# arduino_irobot_bridge.net
KiCad netlist of a schematic drawn in EAGLE
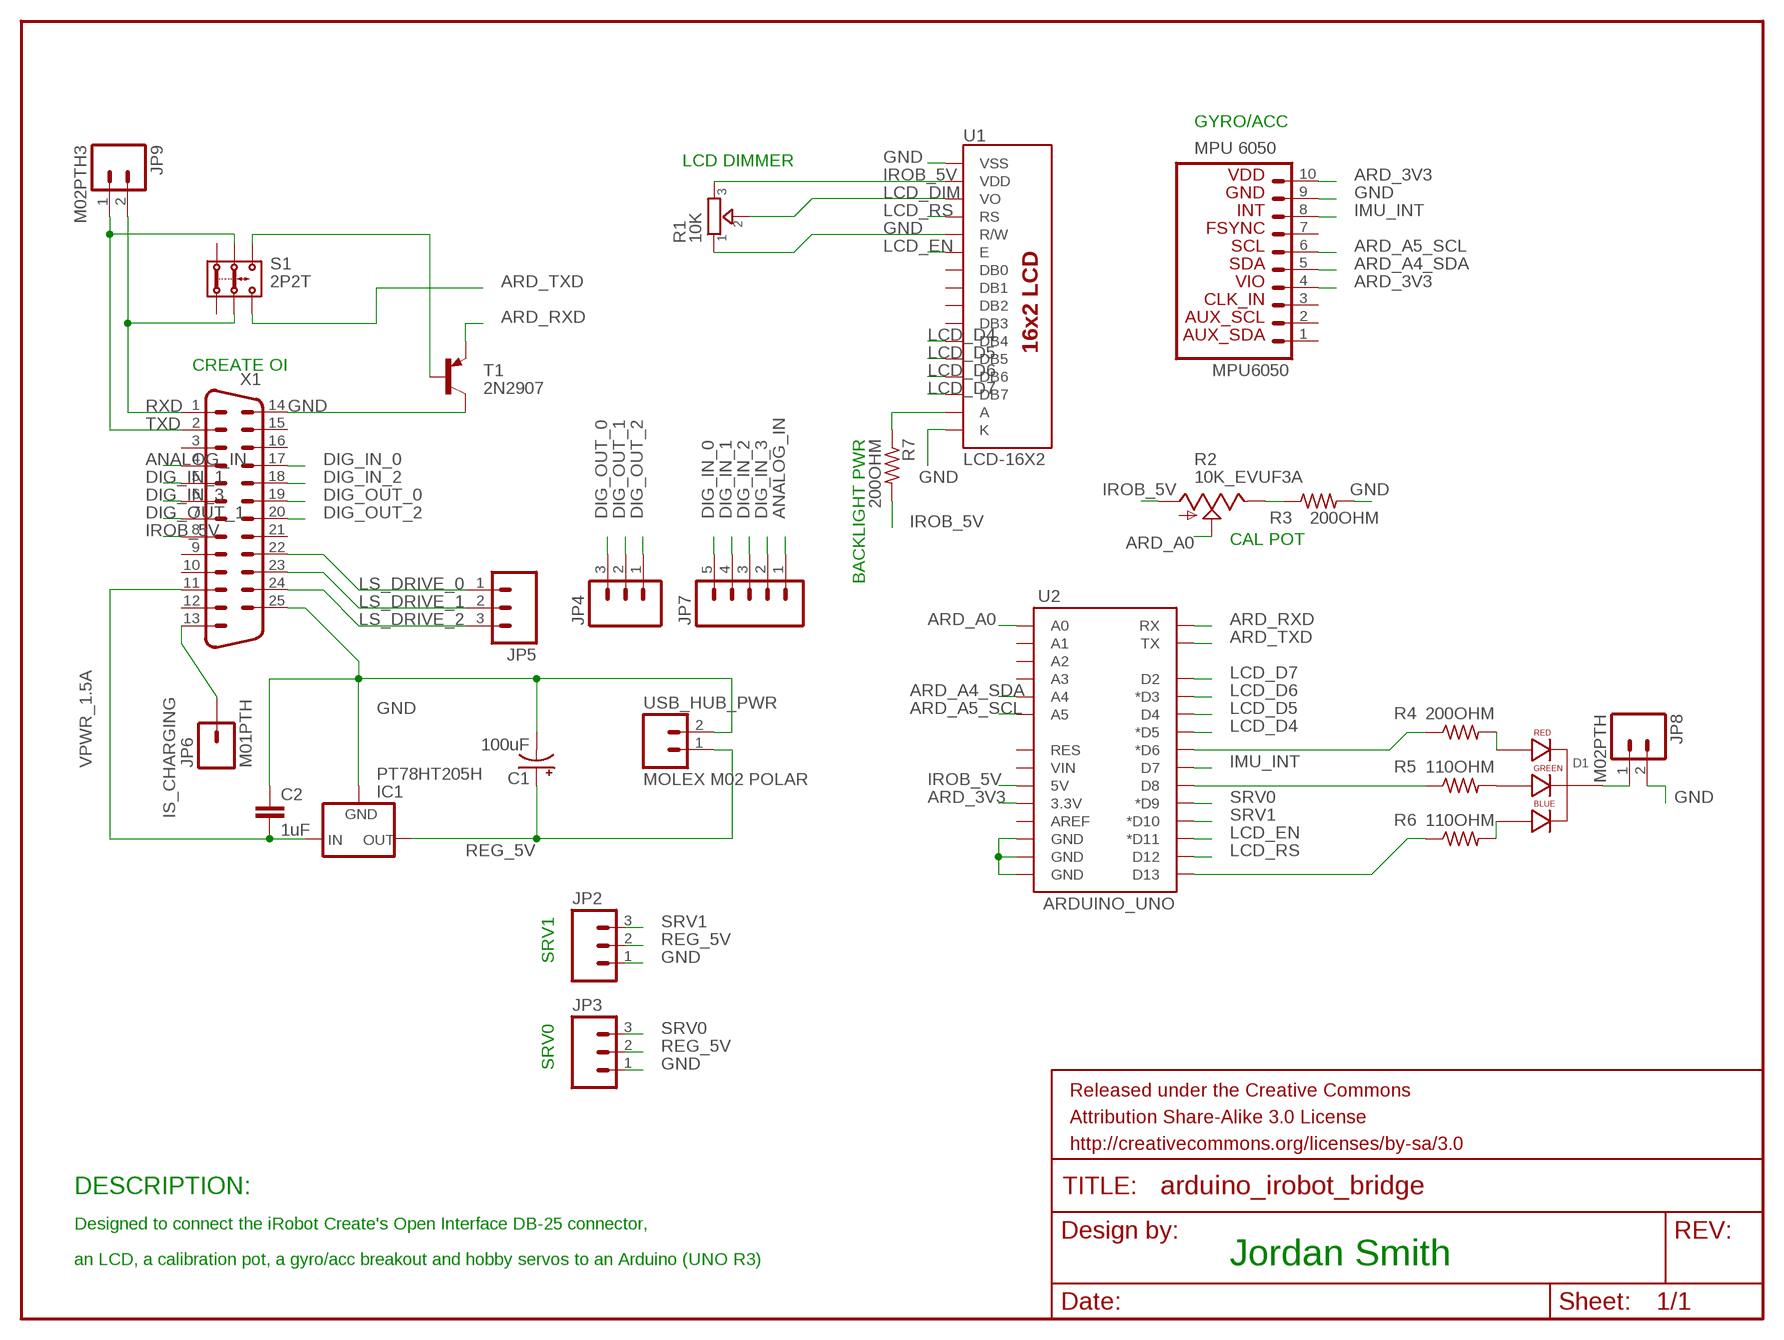
[diagram p0: schematic, sheet 1]

(export (version "E")
  (design (tool "Eeschema 10.0.6"))
  (components
    (comp (ref "C1")
      (value "100uF")
      (footprint "eagle-import:CPOL-RADIAL-100UF-25V")
      (libsource (lib "eagle-import") (part "CAP_POLPTH1"))
    )
    (comp (ref "C2")
      (value "1uF")
      (footprint "eagle-import:C2.5-2")
      (libsource (lib "eagle-import") (part "C2.5/2"))
    )
    (comp (ref "D1")
      (value "LED-RGB-CC-THRUCLEAR")
      (footprint "eagle-import:LED-RGB-THRU")
      (fields (field (name "PROD_ID") "DIO-08418"))
      (libsource (lib "eagle-import") (part "LED-RGB-CC-THRUCLEAR"))
    )
    (comp (ref "FRAME1")
      (value "FRAME-LETTER")
      (footprint "eagle-import:CREATIVE_COMMONS")
      (libsource (lib "eagle-import") (part "FRAME-LETTER"))
    )
    (comp (ref "IC1")
      (value "PT78HT205H")
      (footprint "eagle-import:TO220-IGO")
      (libsource (lib "eagle-import") (part "V_REG_78XXSINK"))
    )
    (comp (ref "JP1")
      (value "MPU6050")
      (footprint "eagle-import:1X10_LOCK_LONGPADS")
      (libsource (lib "eagle-import") (part "M10LOCK_LONGPADS"))
    )
    (comp (ref "JP2")
      (value "M03LOCK_LONGPADS")
      (footprint "eagle-import:1X03_LOCK_LONGPADS")
      (libsource (lib "eagle-import") (part "M03LOCK_LONGPADS"))
    )
    (comp (ref "JP3")
      (value "M03LOCK_LONGPADS")
      (footprint "eagle-import:1X03_LOCK_LONGPADS")
      (libsource (lib "eagle-import") (part "M03LOCK_LONGPADS"))
    )
    (comp (ref "JP4")
      (value "M03LONGPADS")
      (footprint "eagle-import:1X03_LONGPADS")
      (libsource (lib "eagle-import") (part "M03LONGPADS"))
    )
    (comp (ref "JP5")
      (value "M03LONGPADS")
      (footprint "eagle-import:1X03_LONGPADS")
      (libsource (lib "eagle-import") (part "M03LONGPADS"))
    )
    (comp (ref "JP6")
      (value "M01PTH")
      (footprint "eagle-import:1X01")
      (libsource (lib "eagle-import") (part "M01PTH"))
    )
    (comp (ref "JP7")
      (value "M05PTH_LONGPADS")
      (footprint "eagle-import:1X05_LONGPADS")
      (libsource (lib "eagle-import") (part "M05PTH_LONGPADS"))
    )
    (comp (ref "JP8")
      (value "M02PTH")
      (footprint "eagle-import:1X02")
      (libsource (lib "eagle-import") (part "M02PTH"))
    )
    (comp (ref "JP9")
      (value "M02PTH3")
      (footprint "eagle-import:1X02_LONGPADS")
      (libsource (lib "eagle-import") (part "M02PTH3"))
    )
    (comp (ref "R1")
      (value "10K")
      (footprint "eagle-import:TRIMMER_3306F")
      (libsource (lib "eagle-import") (part "TRIMMER-3306F"))
    )
    (comp (ref "R2")
      (value "10K_EVUF3A")
      (footprint "eagle-import:EVUF")
      (libsource (lib "eagle-import") (part "US-EVUAF3"))
    )
    (comp (ref "R3")
      (value "200OHM")
      (footprint "eagle-import:0207_12")
      (libsource (lib "eagle-import") (part "R-US_0207/12"))
    )
    (comp (ref "R4")
      (value "200OHM")
      (footprint "eagle-import:0207_12")
      (libsource (lib "eagle-import") (part "R-US_0207/12"))
    )
    (comp (ref "R5")
      (value "110OHM")
      (footprint "eagle-import:0207_12")
      (libsource (lib "eagle-import") (part "R-US_0207/12"))
    )
    (comp (ref "R6")
      (value "110OHM")
      (footprint "eagle-import:0207_12")
      (libsource (lib "eagle-import") (part "R-US_0207/12"))
    )
    (comp (ref "R7")
      (value "200OHM")
      (footprint "eagle-import:0207_12")
      (libsource (lib "eagle-import") (part "R-US_0207/12"))
    )
    (comp (ref "S1")
      (value "2P2T")
      (footprint "eagle-import:2P2T")
      (libsource (lib "eagle-import") (part "2P2T"))
    )
    (comp (ref "T1")
      (value "2N2907")
      (footprint "eagle-import:TO92-EBC")
      (libsource (lib "eagle-import") (part "-PNP-TO92-EBC"))
    )
    (comp (ref "U1")
      (value "LCD-16X2")
      (footprint "eagle-import:LCD-16X2")
      (libsource (lib "eagle-import") (part "LCD-16X2SILK"))
    )
    (comp (ref "U2")
      (value "ARDUINO_UNO")
      (footprint "eagle-import:DUEMILANOVE_SHIELD")
      (libsource (lib "eagle-import") (part "ARDUINO_SHIELDLABEL"))
    )
    (comp (ref "USB_HUB_PWR")
      (value "MOLEX M02 POLAR")
      (footprint "eagle-import:MOLEX-1X2")
      (libsource (lib "eagle-import") (part "M02POLAR"))
    )
    (comp (ref "X1")
      (value "DB25VP")
      (footprint "eagle-import:M25VP")
      (libsource (lib "eagle-import") (part "DB25VP"))
    )
  )
  (nets
    (net (code "1") (name "/ANALOG_IN") (class "Default")
      (node (ref "JP7") (pin "1") (pinfunction "1_1") (pintype "passive"))
      (node (ref "X1") (pin "4") (pinfunction "4_4") (pintype "passive"))
    )
    (net (code "2") (name "/ARD_3V3") (class "Default")
      (node (ref "JP1") (pin "10") (pinfunction "VDD_3V3_10") (pintype "passive"))
      (node (ref "JP1") (pin "4") (pinfunction "VIO_4") (pintype "passive"))
      (node (ref "U2") (pin "3.3V") (pinfunction "3.3V_3.3V") (pintype "bidirectional"))
    )
    (net (code "3") (name "/ARD_A0") (class "Default")
      (node (ref "R2") (pin "2") (pinfunction "S_2") (pintype "passive"))
      (node (ref "U2") (pin "A0") (pinfunction "A0_A0") (pintype "bidirectional"))
    )
    (net (code "4") (name "/ARD_A4_SDA") (class "Default")
      (node (ref "JP1") (pin "5") (pinfunction "SDA_5") (pintype "passive"))
      (node (ref "U2") (pin "A4") (pinfunction "A4_A4") (pintype "bidirectional"))
    )
    (net (code "5") (name "/ARD_A5_SCL") (class "Default")
      (node (ref "JP1") (pin "6") (pinfunction "SCL_6") (pintype "passive"))
      (node (ref "U2") (pin "A5") (pinfunction "A5_A5") (pintype "bidirectional"))
    )
    (net (code "6") (name "/ARD_RXD") (class "Default")
      (node (ref "T1") (pin "E") (pinfunction "E_E") (pintype "passive"))
      (node (ref "U2") (pin "RX") (pinfunction "RX_RX") (pintype "bidirectional"))
    )
    (net (code "7") (name "/ARD_TXD") (class "Default")
      (node (ref "S1") (pin "3.2") (pinfunction "3.2_3.2") (pintype "passive"))
      (node (ref "U2") (pin "TX") (pinfunction "TX_TX") (pintype "bidirectional"))
    )
    (net (code "8") (name "/DIG_IN_0") (class "Default")
      (node (ref "JP7") (pin "5") (pinfunction "5_5") (pintype "passive"))
      (node (ref "X1") (pin "17") (pinfunction "17_17") (pintype "passive"))
    )
    (net (code "9") (name "/DIG_IN_1") (class "Default")
      (node (ref "JP7") (pin "4") (pinfunction "4_4") (pintype "passive"))
      (node (ref "X1") (pin "5") (pinfunction "5_5") (pintype "passive"))
    )
    (net (code "10") (name "/DIG_IN_2") (class "Default")
      (node (ref "JP7") (pin "3") (pinfunction "3_3") (pintype "passive"))
      (node (ref "X1") (pin "18") (pinfunction "18_18") (pintype "passive"))
    )
    (net (code "11") (name "/DIG_IN_3") (class "Default")
      (node (ref "JP7") (pin "2") (pinfunction "2_2") (pintype "passive"))
      (node (ref "X1") (pin "6") (pinfunction "6_6") (pintype "passive"))
    )
    (net (code "12") (name "/DIG_OUT_0") (class "Default")
      (node (ref "JP4") (pin "3") (pinfunction "3_3") (pintype "passive"))
      (node (ref "X1") (pin "19") (pinfunction "19_19") (pintype "passive"))
    )
    (net (code "13") (name "/DIG_OUT_1") (class "Default")
      (node (ref "JP4") (pin "2") (pinfunction "2_2") (pintype "passive"))
      (node (ref "X1") (pin "7") (pinfunction "7_7") (pintype "passive"))
    )
    (net (code "14") (name "/DIG_OUT_2") (class "Default")
      (node (ref "JP4") (pin "1") (pinfunction "1_1") (pintype "passive"))
      (node (ref "X1") (pin "20") (pinfunction "20_20") (pintype "passive"))
    )
    (net (code "15") (name "/GND") (class "Default")
      (node (ref "C1") (pin "2") (pinfunction "-_2") (pintype "passive"))
      (node (ref "C2") (pin "1") (pinfunction "1_1") (pintype "passive"))
      (node (ref "IC1") (pin "GND") (pinfunction "GND_GND") (pintype "input"))
      (node (ref "JP1") (pin "9") (pinfunction "GND_9") (pintype "passive"))
      (node (ref "JP2") (pin "1") (pinfunction "1_1") (pintype "passive"))
      (node (ref "JP3") (pin "1") (pinfunction "1_1") (pintype "passive"))
      (node (ref "JP8") (pin "2") (pinfunction "2_2") (pintype "passive"))
      (node (ref "R1") (pin "1") (pinfunction "1_1") (pintype "passive"))
      (node (ref "R3") (pin "2") (pinfunction "2_2") (pintype "passive"))
      (node (ref "T1") (pin "C") (pinfunction "C_C") (pintype "passive"))
      (node (ref "U1") (pin "1") (pinfunction "VSS_1") (pintype "power_in"))
      (node (ref "U1") (pin "16") (pinfunction "K_16") (pintype "power_in"))
      (node (ref "U1") (pin "5") (pinfunction "R/W_5") (pintype "input"))
      (node (ref "U2") (pin "GND@0") (pinfunction "GND_GND@0") (pintype "bidirectional"))
      (node (ref "U2") (pin "GND@1") (pinfunction "GND_GND@1") (pintype "bidirectional"))
      (node (ref "U2") (pin "GND@2") (pinfunction "GND_GND@2") (pintype "bidirectional"))
      (node (ref "USB_HUB_PWR") (pin "2") (pinfunction "2_2") (pintype "passive"))
      (node (ref "X1") (pin "14") (pinfunction "14_14") (pintype "passive"))
      (node (ref "X1") (pin "25") (pinfunction "25_25") (pintype "passive"))
    )
    (net (code "16") (name "/IMU_INT") (class "Default")
      (node (ref "JP1") (pin "8") (pinfunction "INT_8") (pintype "passive"))
      (node (ref "U2") (pin "D7") (pinfunction "D7_D7") (pintype "bidirectional"))
    )
    (net (code "17") (name "/IROB_5V") (class "Default")
      (node (ref "R1") (pin "3") (pinfunction "3_3") (pintype "passive"))
      (node (ref "R2") (pin "1") (pinfunction "A_1") (pintype "passive"))
      (node (ref "R7") (pin "2") (pinfunction "2_2") (pintype "passive"))
      (node (ref "U1") (pin "2") (pinfunction "VDD_2") (pintype "power_in"))
      (node (ref "U2") (pin "5V") (pinfunction "5V_5V") (pintype "bidirectional"))
      (node (ref "X1") (pin "8") (pinfunction "8_8") (pintype "passive"))
    )
    (net (code "18") (name "/IS_CHARGING") (class "Default")
      (node (ref "JP6") (pin "1") (pinfunction "1_1") (pintype "passive"))
      (node (ref "X1") (pin "13") (pinfunction "13_13") (pintype "passive"))
    )
    (net (code "19") (name "/LCD_D4") (class "Default")
      (node (ref "U1") (pin "11") (pinfunction "DB4_11") (pintype "bidirectional"))
      (node (ref "U2") (pin "D5") (pinfunction "*D5_D5") (pintype "bidirectional"))
    )
    (net (code "20") (name "/LCD_D5") (class "Default")
      (node (ref "U1") (pin "12") (pinfunction "DB5_12") (pintype "bidirectional"))
      (node (ref "U2") (pin "D4") (pinfunction "D4_D4") (pintype "bidirectional"))
    )
    (net (code "21") (name "/LCD_D6") (class "Default")
      (node (ref "U1") (pin "13") (pinfunction "DB6_13") (pintype "bidirectional"))
      (node (ref "U2") (pin "D3") (pinfunction "*D3_D3") (pintype "bidirectional"))
    )
    (net (code "22") (name "/LCD_D7") (class "Default")
      (node (ref "U1") (pin "14") (pinfunction "DB7_14") (pintype "bidirectional"))
      (node (ref "U2") (pin "D2") (pinfunction "D2_D2") (pintype "bidirectional"))
    )
    (net (code "23") (name "/LCD_DIM") (class "Default")
      (node (ref "R1") (pin "2") (pinfunction "2_2") (pintype "passive"))
      (node (ref "U1") (pin "3") (pinfunction "VO_3") (pintype "bidirectional"))
    )
    (net (code "24") (name "/LCD_EN") (class "Default")
      (node (ref "U1") (pin "6") (pinfunction "E_6") (pintype "input"))
      (node (ref "U2") (pin "D11") (pinfunction "*D11_D11") (pintype "bidirectional"))
    )
    (net (code "25") (name "/LCD_RS") (class "Default")
      (node (ref "U1") (pin "4") (pinfunction "RS_4") (pintype "input"))
      (node (ref "U2") (pin "D12") (pinfunction "D12_D12") (pintype "bidirectional"))
    )
    (net (code "26") (name "/LS_DRIVE_0") (class "Default")
      (node (ref "JP5") (pin "1") (pinfunction "1_1") (pintype "passive"))
      (node (ref "X1") (pin "22") (pinfunction "22_22") (pintype "passive"))
    )
    (net (code "27") (name "/LS_DRIVE_1") (class "Default")
      (node (ref "JP5") (pin "2") (pinfunction "2_2") (pintype "passive"))
      (node (ref "X1") (pin "23") (pinfunction "23_23") (pintype "passive"))
    )
    (net (code "28") (name "/LS_DRIVE_2") (class "Default")
      (node (ref "JP5") (pin "3") (pinfunction "3_3") (pintype "passive"))
      (node (ref "X1") (pin "24") (pinfunction "24_24") (pintype "passive"))
    )
    (net (code "29") (name "/REG_5V") (class "Default")
      (node (ref "C1") (pin "1") (pinfunction "+_1") (pintype "passive"))
      (node (ref "IC1") (pin "OUT") (pinfunction "OUT_OUT") (pintype "output"))
      (node (ref "JP2") (pin "2") (pinfunction "2_2") (pintype "passive"))
      (node (ref "JP3") (pin "2") (pinfunction "2_2") (pintype "passive"))
      (node (ref "USB_HUB_PWR") (pin "1") (pinfunction "1_1") (pintype "passive"))
    )
    (net (code "30") (name "/RXD") (class "Default")
      (node (ref "JP9") (pin "2") (pinfunction "2_2") (pintype "passive"))
      (node (ref "S1") (pin "2.2") (pinfunction "2.2_2.2") (pintype "passive"))
      (node (ref "X1") (pin "1") (pinfunction "1_1") (pintype "passive"))
    )
    (net (code "31") (name "/SRV0") (class "Default")
      (node (ref "JP3") (pin "3") (pinfunction "3_3") (pintype "passive"))
      (node (ref "U2") (pin "D9") (pinfunction "*D9_D9") (pintype "bidirectional"))
    )
    (net (code "32") (name "/SRV1") (class "Default")
      (node (ref "JP2") (pin "3") (pinfunction "3_3") (pintype "passive"))
      (node (ref "U2") (pin "D10") (pinfunction "*D10_D10") (pintype "bidirectional"))
    )
    (net (code "33") (name "/TXD") (class "Default")
      (node (ref "JP9") (pin "1") (pinfunction "1_1") (pintype "passive"))
      (node (ref "S1") (pin "2.1") (pinfunction "2.1_2.1") (pintype "passive"))
      (node (ref "X1") (pin "2") (pinfunction "2_2") (pintype "passive"))
    )
    (net (code "34") (name "/VPWR_1.5A") (class "Default")
      (node (ref "C2") (pin "2") (pinfunction "2_2") (pintype "passive"))
      (node (ref "IC1") (pin "IN") (pinfunction "IN_IN") (pintype "input"))
      (node (ref "X1") (pin "11") (pinfunction "11_11") (pintype "passive"))
    )
    (net (code "35") (name "Net-(D1-BLUE_CATHODE)") (class "Default")
      (node (ref "D1") (pin "4") (pinfunction "BLUE_CATHODE_4") (pintype "bidirectional"))
      (node (ref "R6") (pin "2") (pinfunction "2_2") (pintype "passive"))
    )
    (net (code "36") (name "Net-(D1-CATHODE)") (class "Default")
      (node (ref "D1") (pin "2") (pinfunction "CATHODE_2") (pintype "bidirectional"))
      (node (ref "JP8") (pin "1") (pinfunction "1_1") (pintype "passive"))
    )
    (net (code "37") (name "Net-(D1-GREEN_CATHODE)") (class "Default")
      (node (ref "D1") (pin "3") (pinfunction "GREEN_CATHODE_3") (pintype "bidirectional"))
      (node (ref "R5") (pin "2") (pinfunction "2_2") (pintype "passive"))
    )
    (net (code "38") (name "Net-(D1-RED_CATHODE)") (class "Default")
      (node (ref "D1") (pin "1") (pinfunction "RED_CATHODE_1") (pintype "bidirectional"))
      (node (ref "R4") (pin "2") (pinfunction "2_2") (pintype "passive"))
    )
    (net (code "39") (name "Net-(R2-E)") (class "Default")
      (node (ref "R2") (pin "3") (pinfunction "E_3") (pintype "passive"))
      (node (ref "R3") (pin "1") (pinfunction "1_1") (pintype "passive"))
    )
    (net (code "40") (name "Net-(R5-Pad1)") (class "Default")
      (node (ref "R5") (pin "1") (pinfunction "1_1") (pintype "passive"))
      (node (ref "U2") (pin "D8") (pinfunction "D8_D8") (pintype "bidirectional"))
    )
    (net (code "41") (name "Net-(R6-Pad1)") (class "Default")
      (node (ref "R6") (pin "1") (pinfunction "1_1") (pintype "passive"))
      (node (ref "U2") (pin "D13") (pinfunction "D13_D13") (pintype "bidirectional"))
    )
    (net (code "42") (name "Net-(S1-Pad3.1)") (class "Default")
      (node (ref "S1") (pin "3.1") (pinfunction "3.1_3.1") (pintype "passive"))
      (node (ref "T1") (pin "B") (pinfunction "B_B") (pintype "passive"))
    )
    (net (code "43") (name "Net-(U1-A)") (class "Default")
      (node (ref "R7") (pin "1") (pinfunction "1_1") (pintype "passive"))
      (node (ref "U1") (pin "15") (pinfunction "A_15") (pintype "power_in"))
    )
    (net (code "44") (name "Net-(U2-*D6)") (class "Default")
      (node (ref "R4") (pin "1") (pinfunction "1_1") (pintype "passive"))
      (node (ref "U2") (pin "D6") (pinfunction "*D6_D6") (pintype "bidirectional"))
    )
    (net (code "45") (name "unconnected-(JP1-AUX_SCL-Pad2)") (class "Default")
      (node (ref "JP1") (pin "2") (pinfunction "AUX_SCL_2") (pintype "passive"))
    )
    (net (code "46") (name "unconnected-(JP1-AUX_SDA-Pad1)") (class "Default")
      (node (ref "JP1") (pin "1") (pinfunction "AUX_SDA_1") (pintype "passive"))
    )
    (net (code "47") (name "unconnected-(JP1-CLK_IN-Pad3)") (class "Default")
      (node (ref "JP1") (pin "3") (pinfunction "CLK_IN_3") (pintype "passive"))
    )
    (net (code "48") (name "unconnected-(JP1-FSYNC-Pad7)") (class "Default")
      (node (ref "JP1") (pin "7") (pinfunction "FSYNC_7") (pintype "passive"))
    )
    (net (code "49") (name "unconnected-(S1-Pad1.1)") (class "Default")
      (node (ref "S1") (pin "1.1") (pinfunction "1.1_1.1") (pintype "passive"))
    )
    (net (code "50") (name "unconnected-(S1-Pad1.2)") (class "Default")
      (node (ref "S1") (pin "1.2") (pinfunction "1.2_1.2") (pintype "passive"))
    )
    (net (code "51") (name "unconnected-(U1-DB0-Pad7)") (class "Default")
      (node (ref "U1") (pin "7") (pinfunction "DB0_7") (pintype "bidirectional"))
    )
    (net (code "52") (name "unconnected-(U1-DB1-Pad8)") (class "Default")
      (node (ref "U1") (pin "8") (pinfunction "DB1_8") (pintype "bidirectional"))
    )
    (net (code "53") (name "unconnected-(U1-DB2-Pad9)") (class "Default")
      (node (ref "U1") (pin "9") (pinfunction "DB2_9") (pintype "bidirectional"))
    )
    (net (code "54") (name "unconnected-(U1-DB3-Pad10)") (class "Default")
      (node (ref "U1") (pin "10") (pinfunction "DB3_10") (pintype "bidirectional"))
    )
    (net (code "55") (name "unconnected-(U2-PadA1)") (class "Default")
      (node (ref "U2") (pin "A1") (pinfunction "A1_A1") (pintype "bidirectional"))
    )
    (net (code "56") (name "unconnected-(U2-PadA2)") (class "Default")
      (node (ref "U2") (pin "A2") (pinfunction "A2_A2") (pintype "bidirectional"))
    )
    (net (code "57") (name "unconnected-(U2-PadA3)") (class "Default")
      (node (ref "U2") (pin "A3") (pinfunction "A3_A3") (pintype "bidirectional"))
    )
    (net (code "58") (name "unconnected-(U2-PadAREF)") (class "Default")
      (node (ref "U2") (pin "AREF") (pinfunction "AREF_AREF") (pintype "bidirectional"))
    )
    (net (code "59") (name "unconnected-(U2-PadRES)") (class "Default")
      (node (ref "U2") (pin "RES") (pinfunction "RES_RES") (pintype "bidirectional"))
    )
    (net (code "60") (name "unconnected-(U2-PadVIN)") (class "Default")
      (node (ref "U2") (pin "VIN") (pinfunction "VIN_VIN") (pintype "bidirectional"))
    )
    (net (code "61") (name "unconnected-(X1-Pad3)") (class "Default")
      (node (ref "X1") (pin "3") (pinfunction "3_3") (pintype "passive"))
    )
    (net (code "62") (name "unconnected-(X1-Pad9)") (class "Default")
      (node (ref "X1") (pin "9") (pinfunction "9_9") (pintype "passive"))
    )
    (net (code "63") (name "unconnected-(X1-Pad10)") (class "Default")
      (node (ref "X1") (pin "10") (pinfunction "10_10") (pintype "passive"))
    )
    (net (code "64") (name "unconnected-(X1-Pad12)") (class "Default")
      (node (ref "X1") (pin "12") (pinfunction "12_12") (pintype "passive"))
    )
    (net (code "65") (name "unconnected-(X1-Pad15)") (class "Default")
      (node (ref "X1") (pin "15") (pinfunction "15_15") (pintype "passive"))
    )
    (net (code "66") (name "unconnected-(X1-Pad16)") (class "Default")
      (node (ref "X1") (pin "16") (pinfunction "16_16") (pintype "passive"))
    )
    (net (code "67") (name "unconnected-(X1-Pad21)") (class "Default")
      (node (ref "X1") (pin "21") (pinfunction "21_21") (pintype "passive"))
    )
  )
)
